# multi_sense.net
KiCad netlist of a schematic drawn in EAGLE
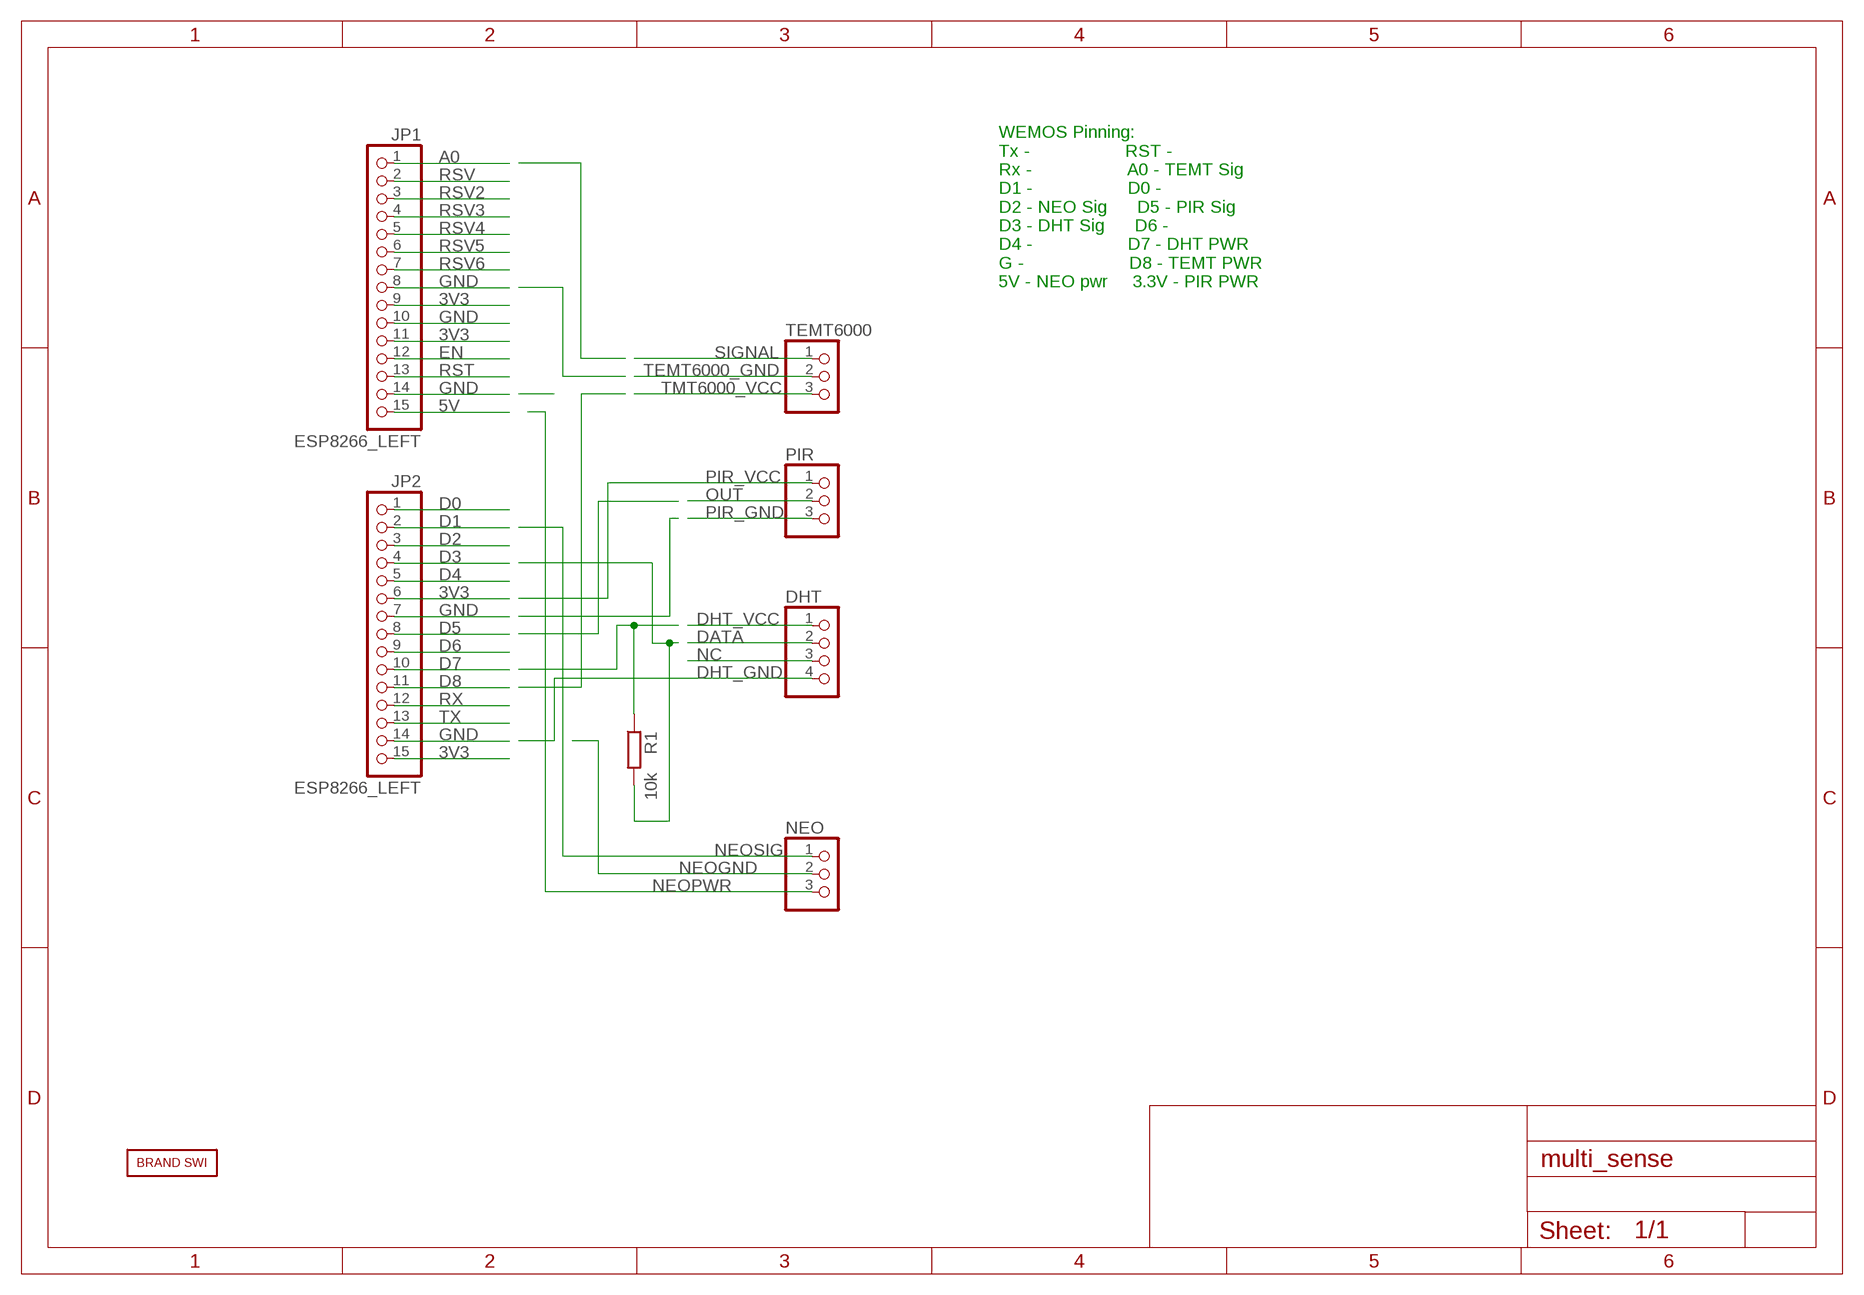
[diagram p0: schematic, sheet 1]

(export (version "E")
  (design (tool "Eeschema 10.0.6"))
  (components
    (comp (ref "DHT")
      (value "PINHD-1X4")
      (footprint "eagle-import:1X04")
      (libsource (lib "eagle-import") (part "PINHD-1X4"))
    )
    (comp (ref "JP1")
      (value "ESP8266_LEFT")
      (footprint "eagle-import:1X15")
      (libsource (lib "eagle-import") (part "PINHD-1X15"))
    )
    (comp (ref "JP2")
      (value "ESP8266_LEFT")
      (footprint "eagle-import:1X15")
      (libsource (lib "eagle-import") (part "PINHD-1X15"))
    )
    (comp (ref "NEO")
      (value "PINHD-1X3")
      (footprint "eagle-import:1X03")
      (libsource (lib "eagle-import") (part "PINHD-1X3"))
    )
    (comp (ref "PIR")
      (value "PINHD-1X3")
      (footprint "eagle-import:1X03")
      (libsource (lib "eagle-import") (part "PINHD-1X3"))
    )
    (comp (ref "R1")
      (value "10k")
      (footprint "eagle-import:0207_10")
      (libsource (lib "eagle-import") (part "R-EU_0207/10"))
    )
    (comp (ref "TEMT6000")
      (value "PINHD-1X3")
      (footprint "eagle-import:1X03")
      (libsource (lib "eagle-import") (part "PINHD-1X3"))
    )
    (comp (ref "U$2")
      (value "BRAND_SWI5X7")
      (footprint "eagle-import:BRAND_SWI_5X7")
      (libsource (lib "eagle-import") (part "BRAND_SWI5X7"))
    )
  )
  (nets
    (net (code "1") (name "/3V3") (class "Default")
      (node (ref "JP1") (pin "11") (pinfunction "11_11") (pintype "passive"))
      (node (ref "JP1") (pin "9") (pinfunction "9_9") (pintype "passive"))
      (node (ref "JP2") (pin "15") (pinfunction "15_15") (pintype "passive"))
      (node (ref "JP2") (pin "6") (pinfunction "6_6") (pintype "passive"))
    )
    (net (code "2") (name "/5V") (class "Default")
      (node (ref "JP1") (pin "15") (pinfunction "15_15") (pintype "passive"))
    )
    (net (code "3") (name "/A0") (class "Default")
      (node (ref "JP1") (pin "1") (pinfunction "1_1") (pintype "passive"))
    )
    (net (code "4") (name "/D0") (class "Default")
      (node (ref "JP2") (pin "1") (pinfunction "1_1") (pintype "passive"))
    )
    (net (code "5") (name "/D1") (class "Default")
      (node (ref "JP2") (pin "2") (pinfunction "2_2") (pintype "passive"))
    )
    (net (code "6") (name "/D2") (class "Default")
      (node (ref "JP2") (pin "3") (pinfunction "3_3") (pintype "passive"))
    )
    (net (code "7") (name "/D3") (class "Default")
      (node (ref "JP2") (pin "4") (pinfunction "4_4") (pintype "passive"))
    )
    (net (code "8") (name "/D4") (class "Default")
      (node (ref "JP2") (pin "5") (pinfunction "5_5") (pintype "passive"))
    )
    (net (code "9") (name "/D5") (class "Default")
      (node (ref "JP2") (pin "8") (pinfunction "8_8") (pintype "passive"))
    )
    (net (code "10") (name "/D6") (class "Default")
      (node (ref "JP2") (pin "9") (pinfunction "9_9") (pintype "passive"))
    )
    (net (code "11") (name "/D7") (class "Default")
      (node (ref "JP2") (pin "10") (pinfunction "10_10") (pintype "passive"))
    )
    (net (code "12") (name "/D8") (class "Default")
      (node (ref "JP2") (pin "11") (pinfunction "11_11") (pintype "passive"))
    )
    (net (code "13") (name "/DATA") (class "Default")
      (node (ref "DHT") (pin "2") (pinfunction "2_2") (pintype "passive"))
    )
    (net (code "14") (name "/DHT_GND") (class "Default")
      (node (ref "DHT") (pin "4") (pinfunction "4_4") (pintype "passive"))
    )
    (net (code "15") (name "/DHT_VCC") (class "Default")
      (node (ref "DHT") (pin "1") (pinfunction "1_1") (pintype "passive"))
    )
    (net (code "16") (name "/EN") (class "Default")
      (node (ref "JP1") (pin "12") (pinfunction "12_12") (pintype "passive"))
    )
    (net (code "17") (name "/GND") (class "Default")
      (node (ref "JP1") (pin "10") (pinfunction "10_10") (pintype "passive"))
      (node (ref "JP1") (pin "14") (pinfunction "14_14") (pintype "passive"))
      (node (ref "JP1") (pin "8") (pinfunction "8_8") (pintype "passive"))
      (node (ref "JP2") (pin "14") (pinfunction "14_14") (pintype "passive"))
      (node (ref "JP2") (pin "7") (pinfunction "7_7") (pintype "passive"))
    )
    (net (code "18") (name "/NC") (class "Default")
      (node (ref "DHT") (pin "3") (pinfunction "3_3") (pintype "passive"))
    )
    (net (code "19") (name "/NEOGND") (class "Default")
      (node (ref "NEO") (pin "2") (pinfunction "2_2") (pintype "passive"))
    )
    (net (code "20") (name "/NEOPWR") (class "Default")
      (node (ref "NEO") (pin "3") (pinfunction "3_3") (pintype "passive"))
    )
    (net (code "21") (name "/NEOSIG") (class "Default")
      (node (ref "NEO") (pin "1") (pinfunction "1_1") (pintype "passive"))
    )
    (net (code "22") (name "/OUT") (class "Default")
      (node (ref "PIR") (pin "2") (pinfunction "2_2") (pintype "passive"))
    )
    (net (code "23") (name "/PIR_GND") (class "Default")
      (node (ref "PIR") (pin "3") (pinfunction "3_3") (pintype "passive"))
    )
    (net (code "24") (name "/PIR_VCC") (class "Default")
      (node (ref "PIR") (pin "1") (pinfunction "1_1") (pintype "passive"))
    )
    (net (code "25") (name "/RST") (class "Default")
      (node (ref "JP1") (pin "13") (pinfunction "13_13") (pintype "passive"))
    )
    (net (code "26") (name "/RSV") (class "Default")
      (node (ref "JP1") (pin "2") (pinfunction "2_2") (pintype "passive"))
    )
    (net (code "27") (name "/RSV2") (class "Default")
      (node (ref "JP1") (pin "3") (pinfunction "3_3") (pintype "passive"))
    )
    (net (code "28") (name "/RSV3") (class "Default")
      (node (ref "JP1") (pin "4") (pinfunction "4_4") (pintype "passive"))
    )
    (net (code "29") (name "/RSV4") (class "Default")
      (node (ref "JP1") (pin "5") (pinfunction "5_5") (pintype "passive"))
    )
    (net (code "30") (name "/RSV5") (class "Default")
      (node (ref "JP1") (pin "6") (pinfunction "6_6") (pintype "passive"))
    )
    (net (code "31") (name "/RSV6") (class "Default")
      (node (ref "JP1") (pin "7") (pinfunction "7_7") (pintype "passive"))
    )
    (net (code "32") (name "/RX") (class "Default")
      (node (ref "JP2") (pin "12") (pinfunction "12_12") (pintype "passive"))
    )
    (net (code "33") (name "/SIGNAL") (class "Default")
      (node (ref "TEMT6000") (pin "1") (pinfunction "1_1") (pintype "passive"))
    )
    (net (code "34") (name "/TEMT6000_GND") (class "Default")
      (node (ref "TEMT6000") (pin "2") (pinfunction "2_2") (pintype "passive"))
    )
    (net (code "35") (name "/TMT6000_VCC") (class "Default")
      (node (ref "TEMT6000") (pin "3") (pinfunction "3_3") (pintype "passive"))
    )
    (net (code "36") (name "/TX") (class "Default")
      (node (ref "JP2") (pin "13") (pinfunction "13_13") (pintype "passive"))
    )
    (net (code "37") (name "unconnected-(R1-Pad1)") (class "Default")
      (node (ref "R1") (pin "1") (pinfunction "1_1") (pintype "passive"))
    )
    (net (code "38") (name "unconnected-(R1-Pad2)") (class "Default")
      (node (ref "R1") (pin "2") (pinfunction "2_2") (pintype "passive"))
    )
  )
)
